# SG_Amplifiers_LTC2053.net
KiCad netlist of a schematic drawn in Altium Designer
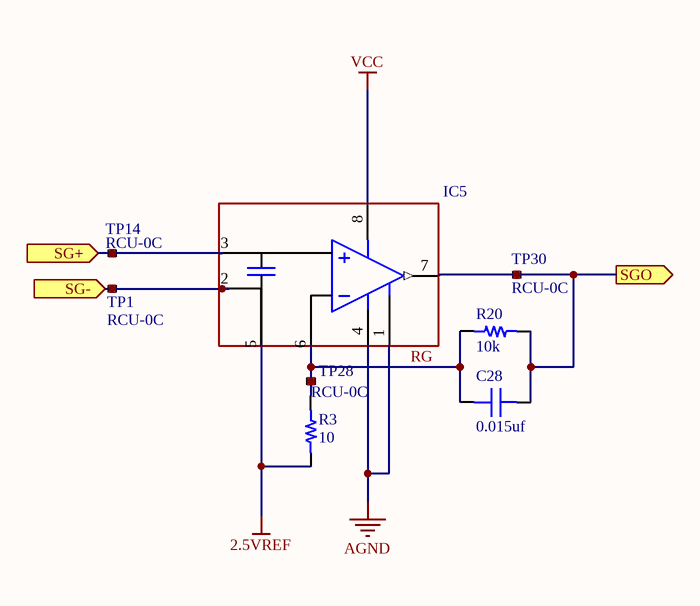
[diagram p0: SG_Amplifiers_LTC2053.SchDoc]

(export (version "E")
  (design (tool "Eeschema 10.0.6"))
  (components
    (comp (ref "C28")
      (value "0.015uf")
      (footprint "CAP 0603/1608")
      (fields
        (field (name "Comment") "Capacitor MLCC 0.015uf 25V CAP 0603/1608")
        (field (name "CREATED_BY") "Nick Mah")
      )
      (libsource (lib "Altium-Lib") (part "Capacitor"))
    )
    (comp (ref "IC5")
      (value "~")
      (footprint "MSOP-8")
      (fields (field (name "MFRPARTNO") "LTC2053") (field (name "CREATED_BY") "Angel Delgado"))
      (libsource (lib "Altium-Lib") (part "Op-Amp LTC2053"))
    )
    (comp (ref "R3")
      (value "10")
      (footprint "RES 0603/1608")
      (fields
        (field (name "TOLERANCE") "1%")
        (field (name "POWER") "1/10W")
        (field (name "Comment") "Resistor 10 0603 1/10W 1%")
        (field (name "CREATED_BY") "Nick Mah")
      )
      (libsource (lib "Altium-Lib") (part "Resistor"))
    )
    (comp (ref "R20")
      (value "10k")
      (footprint "RES 0603/1608")
      (fields
        (field (name "TOLERANCE") "1%")
        (field (name "POWER") "1/10W")
        (field (name "Comment") "Resistor 10k 0603 1/10W 1%")
        (field (name "CREATED_BY") "Nick Mah")
      )
      (libsource (lib "Altium-Lib") (part "Resistor"))
    )
    (comp (ref "TP1")
      (value "RCU-0C")
      (footprint "RCU-0C")
      (description "Test point")
      (fields (field (name "CREATED_BY") "Graydon") (field (name "UPDATED_BY") "Null"))
      (libsource (lib "Altium-Lib") (part "RCU-0C"))
    )
    (comp (ref "TP14")
      (value "RCU-0C")
      (footprint "RCU-0C")
      (description "Test point")
      (fields (field (name "CREATED_BY") "Graydon") (field (name "UPDATED_BY") "Null"))
      (libsource (lib "Altium-Lib") (part "RCU-0C"))
    )
    (comp (ref "TP28")
      (value "RCU-0C")
      (footprint "RCU-0C")
      (description "Test point")
      (fields (field (name "CREATED_BY") "Graydon") (field (name "UPDATED_BY") "Null"))
      (libsource (lib "") (part "RCU-0C_1"))
    )
    (comp (ref "TP30")
      (value "RCU-0C")
      (footprint "RCU-0C")
      (description "Test point")
      (fields (field (name "CREATED_BY") "Graydon") (field (name "UPDATED_BY") "Null"))
      (libsource (lib "") (part "RCU-0C_2"))
    )
  )
  (nets
    (net (code "1") (name "/RG") (class "Default")
      (node (ref "C28") (pin "1") (pinfunction "1_1") (pintype "passive"))
      (node (ref "IC5") (pin "6") (pinfunction "RG_6") (pintype "passive"))
      (node (ref "R20") (pin "1") (pinfunction "1_1") (pintype "passive"))
      (node (ref "R3") (pin "2") (pinfunction "2_2") (pintype "passive"))
      (node (ref "TP28") (pin "1") (pintype "passive"))
    )
    (net (code "2") (name "/SG+") (class "Default")
      (node (ref "IC5") (pin "3") (pinfunction "+IN_3") (pintype "passive"))
      (node (ref "TP14") (pin "1") (pintype "passive"))
    )
    (net (code "3") (name "/SG-") (class "Default")
      (node (ref "IC5") (pin "2") (pinfunction "-IN_2") (pintype "passive"))
      (node (ref "TP1") (pin "1") (pintype "passive"))
    )
    (net (code "4") (name "/SGO") (class "Default")
      (node (ref "C28") (pin "2") (pinfunction "2_2") (pintype "passive"))
      (node (ref "IC5") (pin "7") (pinfunction "OUT_7") (pintype "output"))
      (node (ref "R20") (pin "2") (pinfunction "2_2") (pintype "passive"))
      (node (ref "TP30") (pin "1") (pintype "passive"))
    )
    (net (code "5") (name "2.5VREF") (class "Default")
      (node (ref "IC5") (pin "5") (pinfunction "REF_5") (pintype "passive"))
      (node (ref "R3") (pin "1") (pinfunction "1_1") (pintype "passive"))
    )
    (net (code "6") (name "AGND") (class "Default")
      (node (ref "IC5") (pin "1") (pinfunction "1_1") (pintype "passive"))
      (node (ref "IC5") (pin "4") (pinfunction "V-_4") (pintype "power_in"))
    )
    (net (code "7") (name "VCC") (class "Default")
      (node (ref "IC5") (pin "8") (pinfunction "V+_8") (pintype "power_in"))
    )
  )
)
